# CircuitPlayground-BLE-V1.net
KiCad netlist of a schematic drawn in EAGLE
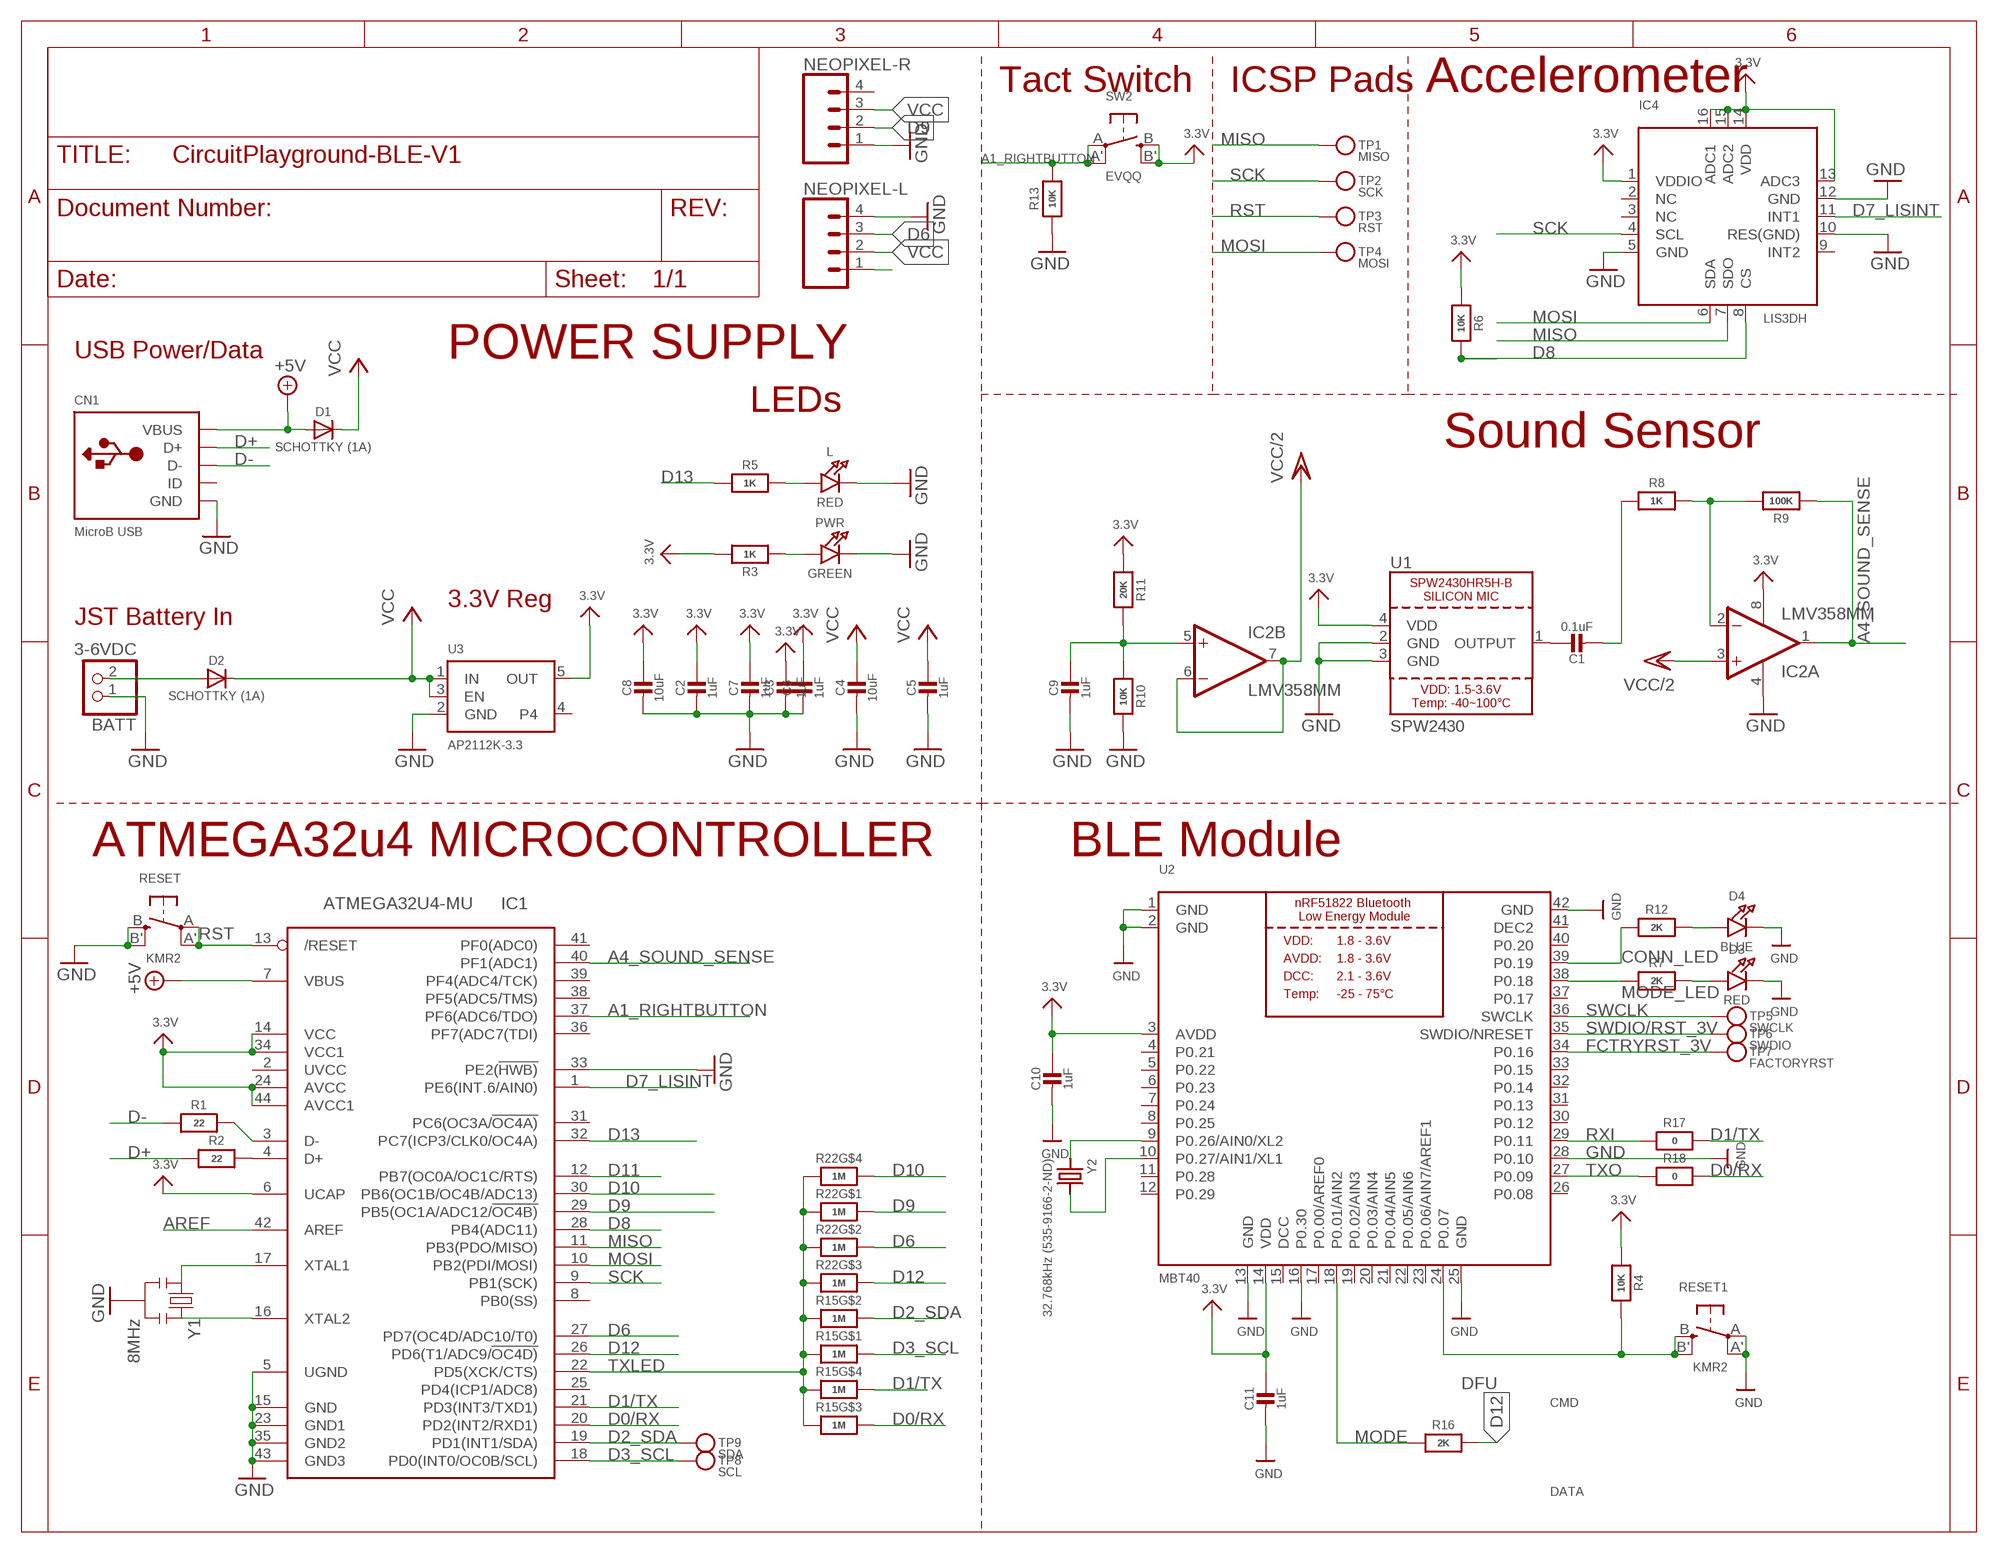
[diagram p0: schematic, sheet 1]

(export (version "E")
  (design (tool "Eeschema 10.0.6"))
  (components
    (comp (ref "BATT")
      (value "3-6VDC")
      (footprint "eagle-import:JSTPH2")
      (libsource (lib "eagle-import") (part "CON_JST_PH_2PIN"))
    )
    (comp (ref "C1")
      (value "0.1uF")
      (footprint "eagle-import:0603-NO")
      (libsource (lib "eagle-import") (part "CAP_CERAMIC0603_NO"))
    )
    (comp (ref "C2")
      (value "1uF")
      (footprint "eagle-import:0603-NO")
      (libsource (lib "eagle-import") (part "CAP_CERAMIC0603_NO"))
    )
    (comp (ref "C3")
      (value "1uF")
      (footprint "eagle-import:0603-NO")
      (libsource (lib "eagle-import") (part "CAP_CERAMIC0603_NO"))
    )
    (comp (ref "C4")
      (value "10uF")
      (footprint "eagle-import:0805-NO")
      (libsource (lib "eagle-import") (part "CAP_CERAMIC0805-NOOUTLINE"))
    )
    (comp (ref "C5")
      (value "1uF")
      (footprint "eagle-import:0603-NO")
      (libsource (lib "eagle-import") (part "CAP_CERAMIC0603_NO"))
    )
    (comp (ref "C6")
      (value "1uF")
      (footprint "eagle-import:0603-NO")
      (libsource (lib "eagle-import") (part "CAP_CERAMIC0603_NO"))
    )
    (comp (ref "C7")
      (value "1uF")
      (footprint "eagle-import:0603-NO")
      (libsource (lib "eagle-import") (part "CAP_CERAMIC0603_NO"))
    )
    (comp (ref "C8")
      (value "10uF")
      (footprint "eagle-import:0805-NO")
      (libsource (lib "eagle-import") (part "CAP_CERAMIC0805-NOOUTLINE"))
    )
    (comp (ref "C9")
      (value "1uF")
      (footprint "eagle-import:0603-NO")
      (libsource (lib "eagle-import") (part "CAP_CERAMIC0603_NO"))
    )
    (comp (ref "C10")
      (value "1uF")
      (footprint "eagle-import:0805-NO")
      (libsource (lib "eagle-import") (part "CAP_CERAMIC0805-NOOUTLINE"))
    )
    (comp (ref "C11")
      (value "1uF")
      (footprint "eagle-import:0805-NO")
      (libsource (lib "eagle-import") (part "CAP_CERAMIC0805-NOOUTLINE"))
    )
    (comp (ref "CN1")
      (value "MicroB USB")
      (footprint "eagle-import:4UCONN_20329_V2")
      (libsource (lib "eagle-import") (part "USB_MICRO_20329_V2"))
    )
    (comp (ref "D1")
      (value "SCHOTTKY (1A)")
      (footprint "eagle-import:SOD-123")
      (libsource (lib "eagle-import") (part "DIODESOD-123"))
    )
    (comp (ref "D2")
      (value "SCHOTTKY (1A)")
      (footprint "eagle-import:SOD-123")
      (libsource (lib "eagle-import") (part "DIODESOD-123"))
    )
    (comp (ref "D3")
      (value "RED")
      (footprint "eagle-import:CHIPLED_0805_NOOUTLINE")
      (libsource (lib "eagle-import") (part "LED0805_NOOUTLINE"))
    )
    (comp (ref "D4")
      (value "BLUE")
      (footprint "eagle-import:CHIPLED_0805_NOOUTLINE")
      (libsource (lib "eagle-import") (part "LED0805_NOOUTLINE"))
    )
    (comp (ref "IC1")
      (value "ATMEGA32U4-MU")
      (footprint "eagle-import:TQFN44_7MM")
      (libsource (lib "eagle-import") (part "ATMEGA32U4-MU"))
    )
    (comp (ref "IC2")
      (value "LMV358MM")
      (footprint "eagle-import:MSOP08")
      (libsource (lib "eagle-import") (part "LMV358?MM"))
    )
    (comp (ref "IC4")
      (value "LIS3DH")
      (footprint "eagle-import:LGA16_3X3MM")
      (libsource (lib "eagle-import") (part "ACCEL_LIS3DHTR"))
    )
    (comp (ref "L")
      (value "RED")
      (footprint "eagle-import:CHIPLED_0805_NOOUTLINE")
      (libsource (lib "eagle-import") (part "LED0805_NOOUTLINE"))
    )
    (comp (ref "NEOPIXEL-L")
      (value "CONN_04")
      (footprint "eagle-import:1X04")
      (libsource (lib "eagle-import") (part "CONN_04"))
    )
    (comp (ref "NEOPIXEL-R")
      (value "CONN_04")
      (footprint "eagle-import:1X04")
      (libsource (lib "eagle-import") (part "CONN_04"))
    )
    (comp (ref "PWR")
      (value "GREEN")
      (footprint "eagle-import:CHIPLED_0805_NOOUTLINE")
      (libsource (lib "eagle-import") (part "LED0805_NOOUTLINE"))
    )
    (comp (ref "R1")
      (value "22")
      (footprint "eagle-import:0603-NO")
      (libsource (lib "eagle-import") (part "RESISTOR_0603_NOOUT"))
    )
    (comp (ref "R2")
      (value "22")
      (footprint "eagle-import:0603-NO")
      (libsource (lib "eagle-import") (part "RESISTOR_0603_NOOUT"))
    )
    (comp (ref "R3")
      (value "1K")
      (footprint "eagle-import:0603-NO")
      (libsource (lib "eagle-import") (part "RESISTOR_0603_NOOUT"))
    )
    (comp (ref "R4")
      (value "10K")
      (footprint "eagle-import:0805-NO")
      (libsource (lib "eagle-import") (part "RESISTOR0805_NOOUTLINE"))
    )
    (comp (ref "R5")
      (value "1K")
      (footprint "eagle-import:0603-NO")
      (libsource (lib "eagle-import") (part "RESISTOR_0603_NOOUT"))
    )
    (comp (ref "R6")
      (value "10K")
      (footprint "eagle-import:0603-NO")
      (libsource (lib "eagle-import") (part "RESISTOR_0603_NOOUT"))
    )
    (comp (ref "R7")
      (value "2K")
      (footprint "eagle-import:0805-NO")
      (libsource (lib "eagle-import") (part "RESISTOR0805_NOOUTLINE"))
    )
    (comp (ref "R8")
      (value "1K")
      (footprint "eagle-import:0603-NO")
      (libsource (lib "eagle-import") (part "RESISTOR_0603_NOOUT"))
    )
    (comp (ref "R9")
      (value "100K")
      (footprint "eagle-import:0603-NO")
      (libsource (lib "eagle-import") (part "RESISTOR_0603_NOOUT"))
    )
    (comp (ref "R10")
      (value "10K")
      (footprint "eagle-import:0603-NO")
      (libsource (lib "eagle-import") (part "RESISTOR_0603_NOOUT"))
    )
    (comp (ref "R11")
      (value "20K")
      (footprint "eagle-import:0603-NO")
      (libsource (lib "eagle-import") (part "RESISTOR_0603_NOOUT"))
    )
    (comp (ref "R12")
      (value "2K")
      (footprint "eagle-import:0805-NO")
      (libsource (lib "eagle-import") (part "RESISTOR0805_NOOUTLINE"))
    )
    (comp (ref "R13")
      (value "10K")
      (footprint "eagle-import:0603-NO")
      (libsource (lib "eagle-import") (part "RESISTOR_0603_NOOUT"))
    )
    (comp (ref "R15")
      (value "1M")
      (footprint "eagle-import:RESPACK_4X0603_NO")
      (libsource (lib "eagle-import") (part "RESISTOR_4PACK_NO"))
    )
    (comp (ref "R16")
      (value "2K")
      (footprint "eagle-import:0805-NO")
      (libsource (lib "eagle-import") (part "RESISTOR0805_NOOUTLINE"))
    )
    (comp (ref "R17")
      (value "0")
      (footprint "eagle-import:0603-NO")
      (libsource (lib "eagle-import") (part "RESISTOR_0603_NOOUT"))
    )
    (comp (ref "R18")
      (value "0")
      (footprint "eagle-import:0603-NO")
      (libsource (lib "eagle-import") (part "RESISTOR_0603_NOOUT"))
    )
    (comp (ref "R22")
      (value "1M")
      (footprint "eagle-import:RESPACK_4X0603_NO")
      (libsource (lib "eagle-import") (part "RESISTOR_4PACK_NO"))
    )
    (comp (ref "RESET")
      (value "KMR2")
      (footprint "eagle-import:BTN_KMR2_4.6X2.8")
      (libsource (lib "eagle-import") (part "SWITCH_TACT_SMT4.6X2.8"))
    )
    (comp (ref "RESET1")
      (value "KMR2")
      (footprint "eagle-import:BTN_KMR2_4.6X2.8")
      (libsource (lib "eagle-import") (part "SWITCH_TACT_SMT4.6X2.8"))
    )
    (comp (ref "SW2")
      (value "EVQQ")
      (footprint "eagle-import:EVQ-Q2_SMALLER")
      (libsource (lib "eagle-import") (part "SWITCH_TACT_SMT_EVQQ2_SMALL"))
    )
    (comp (ref "TP1")
      (value "MISO")
      (footprint "eagle-import:TESTPOINT_ROUND_1.5MM")
      (libsource (lib "eagle-import") (part "TESTPOINTROUND1.5MM"))
    )
    (comp (ref "TP2")
      (value "SCK")
      (footprint "eagle-import:TESTPOINT_ROUND_1.5MM")
      (libsource (lib "eagle-import") (part "TESTPOINTROUND1.5MM"))
    )
    (comp (ref "TP3")
      (value "RST")
      (footprint "eagle-import:TESTPOINT_ROUND_1.5MM")
      (libsource (lib "eagle-import") (part "TESTPOINTROUND1.5MM"))
    )
    (comp (ref "TP4")
      (value "MOSI")
      (footprint "eagle-import:TESTPOINT_ROUND_1.5MM")
      (libsource (lib "eagle-import") (part "TESTPOINTROUND1.5MM"))
    )
    (comp (ref "TP5")
      (value "SWCLK")
      (footprint "eagle-import:TESTPOINT_ROUND_1.5MM")
      (libsource (lib "eagle-import") (part "TESTPOINTROUND1.5MM"))
    )
    (comp (ref "TP6")
      (value "SWDIO")
      (footprint "eagle-import:TESTPOINT_ROUND_1.5MM")
      (libsource (lib "eagle-import") (part "TESTPOINTROUND1.5MM"))
    )
    (comp (ref "TP7")
      (value "FACTORYRST")
      (footprint "eagle-import:TESTPOINT_ROUND_1.5MM")
      (libsource (lib "eagle-import") (part "TESTPOINTROUND1.5MM"))
    )
    (comp (ref "TP8")
      (value "SCL")
      (footprint "eagle-import:TESTPOINT_ROUND_1.5MM")
      (libsource (lib "eagle-import") (part "TESTPOINTROUND1.5MM"))
    )
    (comp (ref "TP9")
      (value "SDA")
      (footprint "eagle-import:TESTPOINT_ROUND_1.5MM")
      (libsource (lib "eagle-import") (part "TESTPOINTROUND1.5MM"))
    )
    (comp (ref "U1")
      (value "SPW2430")
      (footprint "eagle-import:SPW2430HR5H-B")
      (libsource (lib "eagle-import") (part "SPW2430HR5H-B"))
    )
    (comp (ref "U2")
      (value "MBT40")
      (footprint "eagle-import:BLE_MODULE_RAYTAC_MDBT40")
      (libsource (lib "eagle-import") (part "NRF51822_MODULE_MDBT40"))
    )
    (comp (ref "U3")
      (value "AP2112K-3.3")
      (footprint "eagle-import:SOT23-5")
      (libsource (lib "eagle-import") (part "VREG_SOT23-5"))
    )
    (comp (ref "Y1")
      (value "8MHz")
      (footprint "eagle-import:RESONATOR-SMD")
      (libsource (lib "eagle-import") (part "RESONATORSMD"))
    )
    (comp (ref "Y2")
      (value "32.768kHz (535-9166-2-ND)")
      (footprint "eagle-import:CRYSTAL_CYL_2X6MM_SMT")
      (libsource (lib "eagle-import") (part "CRYSTAL2.0X6.0_32.768"))
    )
  )
  (nets
    (net (code "1") (name "+5V") (class "Default")
      (node (ref "CN1") (pin "VBUS") (pinfunction "VBUS_VBUS") (pintype "power_in"))
      (node (ref "D1") (pin "A") (pinfunction "A_A") (pintype "passive"))
      (node (ref "IC1") (pin "7") (pinfunction "VBUS_7") (pintype "bidirectional"))
    )
    (net (code "2") (name "/A1_RIGHTBUTTON") (class "Default")
      (node (ref "IC1") (pin "37") (pinfunction "PF6(ADC6/TDO)_37") (pintype "bidirectional"))
      (node (ref "R13") (pin "2") (pinfunction "2_2") (pintype "passive"))
      (node (ref "SW2") (pin "A") (pinfunction "P_A") (pintype "passive"))
      (node (ref "SW2") (pin "A'") (pinfunction "P1_A'") (pintype "passive"))
    )
    (net (code "3") (name "/A4_SOUND_SENSE") (class "Default")
      (node (ref "IC1") (pin "40") (pinfunction "PF1(ADC1)_40") (pintype "bidirectional"))
      (node (ref "IC2") (pin "1") (pinfunction "OUT_1") (pintype "output"))
      (node (ref "R9") (pin "1") (pinfunction "1_1") (pintype "passive"))
    )
    (net (code "4") (name "/AREF") (class "Default")
      (node (ref "IC1") (pin "42") (pinfunction "AREF_42") (pintype "bidirectional"))
    )
    (net (code "5") (name "/CONN_LED") (class "Default")
      (node (ref "R12") (pin "1") (pinfunction "1_1") (pintype "passive"))
      (node (ref "U2") (pin "39") (pinfunction "P0.19_39") (pintype "bidirectional"))
    )
    (net (code "6") (name "/D+") (class "Default")
      (node (ref "CN1") (pin "D+") (pinfunction "D+_D+") (pintype "bidirectional"))
      (node (ref "R2") (pin "1") (pinfunction "1_1") (pintype "passive"))
    )
    (net (code "7") (name "/D-") (class "Default")
      (node (ref "CN1") (pin "D-") (pinfunction "D-_D-") (pintype "bidirectional"))
      (node (ref "R1") (pin "1") (pinfunction "1_1") (pintype "passive"))
    )
    (net (code "8") (name "/D0{slash}RX") (class "Default")
      (node (ref "IC1") (pin "20") (pinfunction "PD2(INT2/RXD1)_20") (pintype "bidirectional"))
      (node (ref "R15") (pin "6") (pinfunction "2_6") (pintype "passive"))
      (node (ref "R18") (pin "2") (pinfunction "2_2") (pintype "passive"))
    )
    (net (code "9") (name "/D1{slash}TX") (class "Default")
      (node (ref "IC1") (pin "21") (pinfunction "PD3(INT3/TXD1)_21") (pintype "bidirectional"))
      (node (ref "R15") (pin "5") (pinfunction "2_5") (pintype "passive"))
      (node (ref "R17") (pin "2") (pinfunction "2_2") (pintype "passive"))
    )
    (net (code "10") (name "/D2_SDA") (class "Default")
      (node (ref "IC1") (pin "19") (pinfunction "PD1(INT1/SDA)_19") (pintype "bidirectional"))
      (node (ref "R15") (pin "7") (pinfunction "2_7") (pintype "passive"))
      (node (ref "TP9") (pin "P$1") (pinfunction "P$1_P$1") (pintype "bidirectional"))
    )
    (net (code "11") (name "/D3_SCL") (class "Default")
      (node (ref "IC1") (pin "18") (pinfunction "PD0(INT0/OC0B/SCL)_18") (pintype "bidirectional"))
      (node (ref "R15") (pin "8") (pinfunction "2_8") (pintype "passive"))
      (node (ref "TP8") (pin "P$1") (pinfunction "P$1_P$1") (pintype "bidirectional"))
    )
    (net (code "12") (name "/D7_LISINT") (class "Default")
      (node (ref "IC1") (pin "1") (pinfunction "PE6(INT.6/AIN0)_1") (pintype "bidirectional"))
      (node (ref "IC4") (pin "11") (pinfunction "INT1_11") (pintype "output"))
    )
    (net (code "13") (name "/D8") (class "Default")
      (node (ref "IC1") (pin "28") (pinfunction "PB4(ADC11)_28") (pintype "bidirectional"))
      (node (ref "IC4") (pin "8") (pinfunction "CS_8") (pintype "input"))
      (node (ref "R6") (pin "2") (pinfunction "2_2") (pintype "passive"))
    )
    (net (code "14") (name "/D10") (class "Default")
      (node (ref "IC1") (pin "30") (pinfunction "PB6(OC1B/OC4B/ADC13)_30") (pintype "bidirectional"))
      (node (ref "R22") (pin "5") (pinfunction "2_5") (pintype "passive"))
    )
    (net (code "15") (name "/D11") (class "Default")
      (node (ref "IC1") (pin "12") (pinfunction "PB7(OC0A/OC1C/RTS)_12") (pintype "bidirectional"))
    )
    (net (code "16") (name "/D13") (class "Default")
      (node (ref "IC1") (pin "32") (pinfunction "PC7(ICP3/CLK0/OC4A)_32") (pintype "bidirectional"))
      (node (ref "R5") (pin "1") (pinfunction "1_1") (pintype "passive"))
    )
    (net (code "17") (name "/DCC") (class "Default")
      (node (ref "U2") (pin "15") (pinfunction "DCC_15") (pintype "power_in"))
    )
    (net (code "18") (name "/DEC2") (class "Default")
      (node (ref "U2") (pin "41") (pinfunction "DEC2_41") (pintype "power_in"))
    )
    (net (code "19") (name "/DFU") (class "Default")
      (node (ref "R4") (pin "2") (pinfunction "2_2") (pintype "passive"))
      (node (ref "RESET1") (pin "B") (pinfunction "S_B") (pintype "passive"))
      (node (ref "RESET1") (pin "B'") (pinfunction "S1_B'") (pintype "passive"))
      (node (ref "U2") (pin "24") (pinfunction "P0.07_24") (pintype "bidirectional"))
    )
    (net (code "20") (name "/FCTRYRST_3V") (class "Default")
      (node (ref "TP7") (pin "P$1") (pinfunction "P$1_P$1") (pintype "bidirectional"))
      (node (ref "U2") (pin "34") (pinfunction "P0.16_34") (pintype "bidirectional"))
    )
    (net (code "21") (name "/MISO") (class "Default")
      (node (ref "IC1") (pin "11") (pinfunction "PB3(PDO/MISO)_11") (pintype "bidirectional"))
      (node (ref "IC4") (pin "7") (pinfunction "SDO_7") (pintype "bidirectional"))
      (node (ref "TP1") (pin "P$1") (pinfunction "P$1_P$1") (pintype "bidirectional"))
    )
    (net (code "22") (name "/MODE") (class "Default")
      (node (ref "R16") (pin "1") (pinfunction "1_1") (pintype "passive"))
      (node (ref "U2") (pin "18") (pinfunction "P0.01/AIN2_18") (pintype "bidirectional"))
    )
    (net (code "23") (name "/MODE_LED") (class "Default")
      (node (ref "R7") (pin "1") (pinfunction "1_1") (pintype "passive"))
      (node (ref "U2") (pin "38") (pinfunction "P0.18_38") (pintype "bidirectional"))
    )
    (net (code "24") (name "/MOSI") (class "Default")
      (node (ref "IC1") (pin "10") (pinfunction "PB2(PDI/MOSI)_10") (pintype "bidirectional"))
      (node (ref "IC4") (pin "6") (pinfunction "SDA_6") (pintype "bidirectional"))
      (node (ref "TP4") (pin "P$1") (pinfunction "P$1_P$1") (pintype "bidirectional"))
    )
    (net (code "25") (name "/RST") (class "Default")
      (node (ref "IC1") (pin "13") (pinfunction "/RESET_13") (pintype "bidirectional"))
      (node (ref "RESET") (pin "A") (pinfunction "P_A") (pintype "passive"))
      (node (ref "RESET") (pin "A'") (pinfunction "P1_A'") (pintype "passive"))
      (node (ref "TP3") (pin "P$1") (pinfunction "P$1_P$1") (pintype "bidirectional"))
    )
    (net (code "26") (name "/RXI") (class "Default")
      (node (ref "R17") (pin "1") (pinfunction "1_1") (pintype "passive"))
      (node (ref "U2") (pin "29") (pinfunction "P0.11_29") (pintype "bidirectional"))
    )
    (net (code "27") (name "/SCK") (class "Default")
      (node (ref "IC1") (pin "9") (pinfunction "PB1(SCK)_9") (pintype "bidirectional"))
      (node (ref "IC4") (pin "4") (pinfunction "SCL_4") (pintype "bidirectional"))
      (node (ref "TP2") (pin "P$1") (pinfunction "P$1_P$1") (pintype "bidirectional"))
    )
    (net (code "28") (name "/SWCLK") (class "Default")
      (node (ref "TP5") (pin "P$1") (pinfunction "P$1_P$1") (pintype "bidirectional"))
      (node (ref "U2") (pin "36") (pinfunction "SWCLK_36") (pintype "bidirectional"))
    )
    (net (code "29") (name "/SWDIO{slash}RST_3V") (class "Default")
      (node (ref "TP6") (pin "P$1") (pinfunction "P$1_P$1") (pintype "bidirectional"))
      (node (ref "U2") (pin "35") (pinfunction "SWDIO/NRESET_35") (pintype "bidirectional"))
    )
    (net (code "30") (name "/TXLED") (class "Default")
      (node (ref "IC1") (pin "22") (pinfunction "PD5(XCK/CTS)_22") (pintype "bidirectional"))
      (node (ref "R15") (pin "1") (pinfunction "1_1") (pintype "passive"))
      (node (ref "R15") (pin "2") (pinfunction "1_2") (pintype "passive"))
      (node (ref "R15") (pin "3") (pinfunction "1_3") (pintype "passive"))
      (node (ref "R15") (pin "4") (pinfunction "1_4") (pintype "passive"))
      (node (ref "R22") (pin "1") (pinfunction "1_1") (pintype "passive"))
      (node (ref "R22") (pin "2") (pinfunction "1_2") (pintype "passive"))
      (node (ref "R22") (pin "3") (pinfunction "1_3") (pintype "passive"))
      (node (ref "R22") (pin "4") (pinfunction "1_4") (pintype "passive"))
    )
    (net (code "31") (name "/TXO") (class "Default")
      (node (ref "R18") (pin "1") (pinfunction "1_1") (pintype "passive"))
      (node (ref "U2") (pin "27") (pinfunction "P0.09_27") (pintype "bidirectional"))
    )
    (net (code "32") (name "3.3V") (class "Default")
      (node (ref "C10") (pin "1") (pinfunction "1_1") (pintype "passive"))
      (node (ref "C11") (pin "1") (pinfunction "1_1") (pintype "passive"))
      (node (ref "C2") (pin "1") (pinfunction "1_1") (pintype "passive"))
      (node (ref "C3") (pin "1") (pinfunction "1_1") (pintype "passive"))
      (node (ref "C6") (pin "1") (pinfunction "1_1") (pintype "passive"))
      (node (ref "C7") (pin "1") (pinfunction "1_1") (pintype "passive"))
      (node (ref "C8") (pin "1") (pinfunction "1_1") (pintype "passive"))
      (node (ref "IC1") (pin "14") (pinfunction "VCC_14") (pintype "bidirectional"))
      (node (ref "IC1") (pin "24") (pinfunction "AVCC_24") (pintype "bidirectional"))
      (node (ref "IC1") (pin "34") (pinfunction "VCC1_34") (pintype "bidirectional"))
      (node (ref "IC1") (pin "44") (pinfunction "AVCC1_44") (pintype "bidirectional"))
      (node (ref "IC1") (pin "6") (pinfunction "UCAP_6") (pintype "bidirectional"))
      (node (ref "IC2") (pin "8") (pinfunction "V+_8") (pintype "power_in"))
      (node (ref "IC4") (pin "1") (pinfunction "VDDIO_1") (pintype "power_in"))
      (node (ref "IC4") (pin "13") (pinfunction "ADC3_13") (pintype "input"))
      (node (ref "IC4") (pin "14") (pinfunction "VDD_14") (pintype "power_in"))
      (node (ref "IC4") (pin "15") (pinfunction "ADC2_15") (pintype "input"))
      (node (ref "IC4") (pin "16") (pinfunction "ADC1_16") (pintype "input"))
      (node (ref "NEOPIXEL-L") (pin "1") (pinfunction "1_1") (pintype "passive"))
      (node (ref "R11") (pin "1") (pinfunction "1_1") (pintype "passive"))
      (node (ref "R3") (pin "2") (pinfunction "2_2") (pintype "passive"))
      (node (ref "R4") (pin "1") (pinfunction "1_1") (pintype "passive"))
      (node (ref "R6") (pin "1") (pinfunction "1_1") (pintype "passive"))
      (node (ref "SW2") (pin "B") (pinfunction "S_B") (pintype "passive"))
      (node (ref "SW2") (pin "B'") (pinfunction "S1_B'") (pintype "passive"))
      (node (ref "U1") (pin "4") (pinfunction "VDD_4") (pintype "power_in"))
      (node (ref "U2") (pin "14") (pinfunction "VDD_14") (pintype "power_in"))
      (node (ref "U2") (pin "3") (pinfunction "AVDD_3") (pintype "power_in"))
      (node (ref "U3") (pin "5") (pinfunction "OUT_5") (pintype "power_in"))
    )
    (net (code "33") (name "D6") (class "Default")
      (node (ref "IC1") (pin "27") (pinfunction "PD7(OC4D/ADC10/T0)_27") (pintype "bidirectional"))
      (node (ref "NEOPIXEL-L") (pin "3") (pinfunction "3_3") (pintype "passive"))
      (node (ref "R22") (pin "7") (pinfunction "2_7") (pintype "passive"))
    )
    (net (code "34") (name "D9") (class "Default")
      (node (ref "IC1") (pin "29") (pinfunction "PB5(OC1A/ADC12/~{OC4B})_29") (pintype "bidirectional"))
      (node (ref "NEOPIXEL-R") (pin "2") (pinfunction "2_2") (pintype "passive"))
      (node (ref "R22") (pin "8") (pinfunction "2_8") (pintype "passive"))
    )
    (net (code "35") (name "D12") (class "Default")
      (node (ref "IC1") (pin "26") (pinfunction "PD6(T1/ADC9/~{OC4D})_26") (pintype "bidirectional"))
      (node (ref "R16") (pin "2") (pinfunction "2_2") (pintype "passive"))
      (node (ref "R22") (pin "6") (pinfunction "2_6") (pintype "passive"))
    )
    (net (code "36") (name "GND") (class "Default")
      (node (ref "BATT") (pin "1") (pinfunction "1_1") (pintype "passive"))
      (node (ref "C10") (pin "2") (pinfunction "2_2") (pintype "passive"))
      (node (ref "C11") (pin "2") (pinfunction "2_2") (pintype "passive"))
      (node (ref "C2") (pin "2") (pinfunction "2_2") (pintype "passive"))
      (node (ref "C3") (pin "2") (pinfunction "2_2") (pintype "passive"))
      (node (ref "C4") (pin "2") (pinfunction "2_2") (pintype "passive"))
      (node (ref "C5") (pin "2") (pinfunction "2_2") (pintype "passive"))
      (node (ref "C6") (pin "2") (pinfunction "2_2") (pintype "passive"))
      (node (ref "C7") (pin "2") (pinfunction "2_2") (pintype "passive"))
      (node (ref "C8") (pin "2") (pinfunction "2_2") (pintype "passive"))
      (node (ref "C9") (pin "2") (pinfunction "2_2") (pintype "passive"))
      (node (ref "CN1") (pin "BASE@1") (pinfunction "GND_BASE@1") (pintype "power_in"))
      (node (ref "CN1") (pin "BASE@2") (pinfunction "GND_BASE@2") (pintype "power_in"))
      (node (ref "CN1") (pin "GND") (pinfunction "GND_GND") (pintype "power_in"))
      (node (ref "CN1") (pin "SPRT@1") (pinfunction "GND_SPRT@1") (pintype "power_in"))
      (node (ref "CN1") (pin "SPRT@2") (pinfunction "GND_SPRT@2") (pintype "power_in"))
      (node (ref "CN1") (pin "SPRT@3") (pinfunction "GND_SPRT@3") (pintype "power_in"))
      (node (ref "CN1") (pin "SPRT@4") (pinfunction "GND_SPRT@4") (pintype "power_in"))
      (node (ref "D3") (pin "C") (pinfunction "C_C") (pintype "passive"))
      (node (ref "D4") (pin "C") (pinfunction "C_C") (pintype "passive"))
      (node (ref "IC1") (pin "15") (pinfunction "GND_15") (pintype "bidirectional"))
      (node (ref "IC1") (pin "23") (pinfunction "GND1_23") (pintype "bidirectional"))
      (node (ref "IC1") (pin "33") (pinfunction "PE2(~{HWB})_33") (pintype "bidirectional"))
      (node (ref "IC1") (pin "35") (pinfunction "GND2_35") (pintype "bidirectional"))
      (node (ref "IC1") (pin "43") (pinfunction "GND3_43") (pintype "bidirectional"))
      (node (ref "IC1") (pin "5") (pinfunction "UGND_5") (pintype "bidirectional"))
      (node (ref "IC2") (pin "4") (pinfunction "V-_4") (pintype "power_in"))
      (node (ref "IC4") (pin "10") (pinfunction "RES(GND)_10") (pintype "bidirectional"))
      (node (ref "IC4") (pin "12") (pinfunction "GND_12") (pintype "power_in"))
      (node (ref "IC4") (pin "5") (pinfunction "GND_5") (pintype "power_in"))
      (node (ref "L") (pin "C") (pinfunction "C_C") (pintype "passive"))
      (node (ref "NEOPIXEL-L") (pin "4") (pinfunction "4_4") (pintype "passive"))
      (node (ref "NEOPIXEL-R") (pin "1") (pinfunction "1_1") (pintype "passive"))
      (node (ref "PWR") (pin "C") (pinfunction "C_C") (pintype "passive"))
      (node (ref "R10") (pin "2") (pinfunction "2_2") (pintype "passive"))
      (node (ref "R13") (pin "1") (pinfunction "1_1") (pintype "passive"))
      (node (ref "RESET") (pin "B") (pinfunction "S_B") (pintype "passive"))
      (node (ref "RESET") (pin "B'") (pinfunction "S1_B'") (pintype "passive"))
      (node (ref "RESET1") (pin "A") (pinfunction "P_A") (pintype "passive"))
      (node (ref "RESET1") (pin "A'") (pinfunction "P1_A'") (pintype "passive"))
      (node (ref "U1") (pin "2") (pinfunction "GND_2") (pintype "power_in"))
      (node (ref "U1") (pin "3") (pinfunction "GND_3") (pintype "power_in"))
      (node (ref "U2") (pin "1") (pinfunction "GND_1") (pintype "power_in"))
      (node (ref "U2") (pin "13") (pinfunction "GND_13") (pintype "power_in"))
      (node (ref "U2") (pin "16") (pinfunction "P0.30_16") (pintype "bidirectional"))
      (node (ref "U2") (pin "2") (pinfunction "GND_2") (pintype "power_in"))
      (node (ref "U2") (pin "25") (pinfunction "GND_25") (pintype "power_in"))
      (node (ref "U2") (pin "28") (pinfunction "P0.10_28") (pintype "bidirectional"))
      (node (ref "U2") (pin "42") (pinfunction "GND_42") (pintype "power_in"))
      (node (ref "U3") (pin "2") (pinfunction "GND_2") (pintype "power_in"))
      (node (ref "Y1") (pin "2") (pinfunction "2_2") (pintype "passive"))
    )
    (net (code "37") (name "Net-(BATT-Pad2)") (class "Default")
      (node (ref "BATT") (pin "2") (pinfunction "2_2") (pintype "passive"))
      (node (ref "D2") (pin "A") (pinfunction "A_A") (pintype "passive"))
    )
    (net (code "38") (name "Net-(C1-Pad2)") (class "Default")
      (node (ref "C1") (pin "2") (pinfunction "2_2") (pintype "passive"))
      (node (ref "R8") (pin "1") (pinfunction "1_1") (pintype "passive"))
    )
    (net (code "39") (name "Net-(D3-PadA)") (class "Default")
      (node (ref "D3") (pin "A") (pinfunction "A_A") (pintype "passive"))
      (node (ref "R7") (pin "2") (pinfunction "2_2") (pintype "passive"))
    )
    (net (code "40") (name "Net-(D4-PadA)") (class "Default")
      (node (ref "D4") (pin "A") (pinfunction "A_A") (pintype "passive"))
      (node (ref "R12") (pin "2") (pinfunction "2_2") (pintype "passive"))
    )
    (net (code "41") (name "Net-(IC1-D+)") (class "Default")
      (node (ref "IC1") (pin "4") (pinfunction "D+_4") (pintype "bidirectional"))
      (node (ref "R2") (pin "2") (pinfunction "2_2") (pintype "passive"))
    )
    (net (code "42") (name "Net-(IC1-D-)") (class "Default")
      (node (ref "IC1") (pin "3") (pinfunction "D-_3") (pintype "bidirectional"))
      (node (ref "R1") (pin "2") (pinfunction "2_2") (pintype "passive"))
    )
    (net (code "43") (name "Net-(IC1-XTAL1)") (class "Default")
      (node (ref "IC1") (pin "17") (pinfunction "XTAL1_17") (pintype "bidirectional"))
      (node (ref "Y1") (pin "1") (pinfunction "1_1") (pintype "passive"))
    )
    (net (code "44") (name "Net-(IC1-XTAL2)") (class "Default")
      (node (ref "IC1") (pin "16") (pinfunction "XTAL2_16") (pintype "bidirectional"))
      (node (ref "Y1") (pin "3") (pinfunction "3_3") (pintype "passive"))
    )
    (net (code "45") (name "Net-(IC2A--IN)") (class "Default")
      (node (ref "IC2") (pin "2") (pinfunction "-IN_2") (pintype "input"))
      (node (ref "R8") (pin "2") (pinfunction "2_2") (pintype "passive"))
      (node (ref "R9") (pin "2") (pinfunction "2_2") (pintype "passive"))
    )
    (net (code "46") (name "Net-(IC2B-+IN)") (class "Default")
      (node (ref "C9") (pin "1") (pinfunction "1_1") (pintype "passive"))
      (node (ref "IC2") (pin "5") (pinfunction "+IN_5") (pintype "input"))
      (node (ref "R10") (pin "1") (pinfunction "1_1") (pintype "passive"))
      (node (ref "R11") (pin "2") (pinfunction "2_2") (pintype "passive"))
    )
    (net (code "47") (name "Net-(L-PadA)") (class "Default")
      (node (ref "L") (pin "A") (pinfunction "A_A") (pintype "passive"))
      (node (ref "R5") (pin "2") (pinfunction "2_2") (pintype "passive"))
    )
    (net (code "48") (name "Net-(PWR-PadA)") (class "Default")
      (node (ref "PWR") (pin "A") (pinfunction "A_A") (pintype "passive"))
      (node (ref "R3") (pin "1") (pinfunction "1_1") (pintype "passive"))
    )
    (net (code "49") (name "Net-(U1-OUTPUT)") (class "Default")
      (node (ref "C1") (pin "1") (pinfunction "1_1") (pintype "passive"))
      (node (ref "U1") (pin "1") (pinfunction "OUTPUT_1") (pintype "output"))
    )
    (net (code "50") (name "Net-(U2-P0.26{slash}AIN0{slash}XL2)") (class "Default")
      (node (ref "U2") (pin "9") (pinfunction "P0.26/AIN0/XL2_9") (pintype "bidirectional"))
      (node (ref "Y2") (pin "1") (pinfunction "1_1") (pintype "passive"))
    )
    (net (code "51") (name "Net-(U2-P0.27{slash}AIN1{slash}XL1)") (class "Default")
      (node (ref "U2") (pin "10") (pinfunction "P0.27/AIN1/XL1_10") (pintype "bidirectional"))
      (node (ref "Y2") (pin "2") (pinfunction "2_2") (pintype "passive"))
    )
    (net (code "52") (name "VCC") (class "Default")
      (node (ref "C4") (pin "1") (pinfunction "1_1") (pintype "passive"))
      (node (ref "C5") (pin "1") (pinfunction "1_1") (pintype "passive"))
      (node (ref "D1") (pin "C") (pinfunction "C_C") (pintype "passive"))
      (node (ref "D2") (pin "C") (pinfunction "C_C") (pintype "passive"))
      (node (ref "NEOPIXEL-L") (pin "2") (pinfunction "2_2") (pintype "passive"))
      (node (ref "NEOPIXEL-R") (pin "3") (pinfunction "3_3") (pintype "passive"))
      (node (ref "U3") (pin "1") (pinfunction "IN_1") (pintype "power_in"))
      (node (ref "U3") (pin "3") (pinfunction "EN_3") (pintype "input"))
    )
    (net (code "53") (name "VCC{slash}2") (class "Default")
      (node (ref "IC2") (pin "3") (pinfunction "+IN_3") (pintype "input"))
      (node (ref "IC2") (pin "6") (pinfunction "-IN_6") (pintype "input"))
      (node (ref "IC2") (pin "7") (pinfunction "OUT_7") (pintype "output"))
    )
    (net (code "54") (name "unconnected-(CN1-PadID)") (class "Default")
      (node (ref "CN1") (pin "ID") (pinfunction "ID_ID") (pintype "bidirectional"))
    )
    (net (code "55") (name "unconnected-(IC1-PB0(SS)-Pad8)") (class "Default")
      (node (ref "IC1") (pin "8") (pinfunction "PB0(SS)_8") (pintype "bidirectional"))
    )
    (net (code "56") (name "unconnected-(IC1-PC6(OC3A{slash}~{OC4A})-Pad31)") (class "Default")
      (node (ref "IC1") (pin "31") (pinfunction "PC6(OC3A/~{OC4A})_31") (pintype "bidirectional"))
    )
    (net (code "57") (name "unconnected-(IC1-PD4(ICP1{slash}ADC8)-Pad25)") (class "Default")
      (node (ref "IC1") (pin "25") (pinfunction "PD4(ICP1/ADC8)_25") (pintype "bidirectional"))
    )
    (net (code "58") (name "unconnected-(IC1-PF0(ADC0)-Pad41)") (class "Default")
      (node (ref "IC1") (pin "41") (pinfunction "PF0(ADC0)_41") (pintype "bidirectional"))
    )
    (net (code "59") (name "unconnected-(IC1-PF4(ADC4{slash}TCK)-Pad39)") (class "Default")
      (node (ref "IC1") (pin "39") (pinfunction "PF4(ADC4/TCK)_39") (pintype "bidirectional"))
    )
    (net (code "60") (name "unconnected-(IC1-PF5(ADC5{slash}TMS)-Pad38)") (class "Default")
      (node (ref "IC1") (pin "38") (pinfunction "PF5(ADC5/TMS)_38") (pintype "bidirectional"))
    )
    (net (code "61") (name "unconnected-(IC1-PF7(ADC7(TDI)-Pad36)") (class "Default")
      (node (ref "IC1") (pin "36") (pinfunction "PF7(ADC7(TDI)_36") (pintype "bidirectional"))
    )
    (net (code "62") (name "unconnected-(IC1-UVCC-Pad2)") (class "Default")
      (node (ref "IC1") (pin "2") (pinfunction "UVCC_2") (pintype "bidirectional"))
    )
    (net (code "63") (name "unconnected-(IC4-INT2-Pad9)") (class "Default")
      (node (ref "IC4") (pin "9") (pinfunction "INT2_9") (pintype "output"))
    )
    (net (code "64") (name "unconnected-(IC4-NC-Pad2)") (class "Default")
      (node (ref "IC4") (pin "2") (pinfunction "NC_2") (pintype "no_connect"))
    )
    (net (code "65") (name "unconnected-(IC4-NC-Pad3)") (class "Default")
      (node (ref "IC4") (pin "3") (pinfunction "NC_3") (pintype "no_connect"))
    )
    (net (code "66") (name "unconnected-(NEOPIXEL-R-Pad4)") (class "Default")
      (node (ref "NEOPIXEL-R") (pin "4") (pinfunction "4_4") (pintype "passive"))
    )
    (net (code "67") (name "unconnected-(U2-P0.00{slash}AREF0-Pad17)") (class "Default")
      (node (ref "U2") (pin "17") (pinfunction "P0.00/AREF0_17") (pintype "bidirectional"))
    )
    (net (code "68") (name "unconnected-(U2-P0.02{slash}AIN3-Pad19)") (class "Default")
      (node (ref "U2") (pin "19") (pinfunction "P0.02/AIN3_19") (pintype "bidirectional"))
    )
    (net (code "69") (name "unconnected-(U2-P0.03{slash}AIN4-Pad20)") (class "Default")
      (node (ref "U2") (pin "20") (pinfunction "P0.03/AIN4_20") (pintype "bidirectional"))
    )
    (net (code "70") (name "unconnected-(U2-P0.04{slash}AIN5-Pad21)") (class "Default")
      (node (ref "U2") (pin "21") (pinfunction "P0.04/AIN5_21") (pintype "bidirectional"))
    )
    (net (code "71") (name "unconnected-(U2-P0.05{slash}AIN6-Pad22)") (class "Default")
      (node (ref "U2") (pin "22") (pinfunction "P0.05/AIN6_22") (pintype "bidirectional"))
    )
    (net (code "72") (name "unconnected-(U2-P0.06{slash}AIN7{slash}AREF1-Pad23)") (class "Default")
      (node (ref "U2") (pin "23") (pinfunction "P0.06/AIN7/AREF1_23") (pintype "bidirectional"))
    )
    (net (code "73") (name "unconnected-(U2-P0.08-Pad26)") (class "Default")
      (node (ref "U2") (pin "26") (pinfunction "P0.08_26") (pintype "bidirectional"))
    )
    (net (code "74") (name "unconnected-(U2-P0.12-Pad30)") (class "Default")
      (node (ref "U2") (pin "30") (pinfunction "P0.12_30") (pintype "bidirectional"))
    )
    (net (code "75") (name "unconnected-(U2-P0.13-Pad31)") (class "Default")
      (node (ref "U2") (pin "31") (pinfunction "P0.13_31") (pintype "bidirectional"))
    )
    (net (code "76") (name "unconnected-(U2-P0.14-Pad32)") (class "Default")
      (node (ref "U2") (pin "32") (pinfunction "P0.14_32") (pintype "bidirectional"))
    )
    (net (code "77") (name "unconnected-(U2-P0.15-Pad33)") (class "Default")
      (node (ref "U2") (pin "33") (pinfunction "P0.15_33") (pintype "bidirectional"))
    )
    (net (code "78") (name "unconnected-(U2-P0.17-Pad37)") (class "Default")
      (node (ref "U2") (pin "37") (pinfunction "P0.17_37") (pintype "bidirectional"))
    )
    (net (code "79") (name "unconnected-(U2-P0.20-Pad40)") (class "Default")
      (node (ref "U2") (pin "40") (pinfunction "P0.20_40") (pintype "bidirectional"))
    )
    (net (code "80") (name "unconnected-(U2-P0.21-Pad4)") (class "Default")
      (node (ref "U2") (pin "4") (pinfunction "P0.21_4") (pintype "bidirectional"))
    )
    (net (code "81") (name "unconnected-(U2-P0.22-Pad5)") (class "Default")
      (node (ref "U2") (pin "5") (pinfunction "P0.22_5") (pintype "bidirectional"))
    )
    (net (code "82") (name "unconnected-(U2-P0.23-Pad6)") (class "Default")
      (node (ref "U2") (pin "6") (pinfunction "P0.23_6") (pintype "bidirectional"))
    )
    (net (code "83") (name "unconnected-(U2-P0.24-Pad7)") (class "Default")
      (node (ref "U2") (pin "7") (pinfunction "P0.24_7") (pintype "bidirectional"))
    )
    (net (code "84") (name "unconnected-(U2-P0.25-Pad8)") (class "Default")
      (node (ref "U2") (pin "8") (pinfunction "P0.25_8") (pintype "bidirectional"))
    )
    (net (code "85") (name "unconnected-(U2-P0.28-Pad11)") (class "Default")
      (node (ref "U2") (pin "11") (pinfunction "P0.28_11") (pintype "bidirectional"))
    )
    (net (code "86") (name "unconnected-(U2-P0.29-Pad12)") (class "Default")
      (node (ref "U2") (pin "12") (pinfunction "P0.29_12") (pintype "bidirectional"))
    )
    (net (code "87") (name "unconnected-(U3-P4-Pad4)") (class "Default")
      (node (ref "U3") (pin "4") (pinfunction "P4_4") (pintype "bidirectional"))
    )
  )
)
